# Attenuverting_Mixer_Slim_main_v1.net
KiCad netlist of a schematic drawn in EAGLE
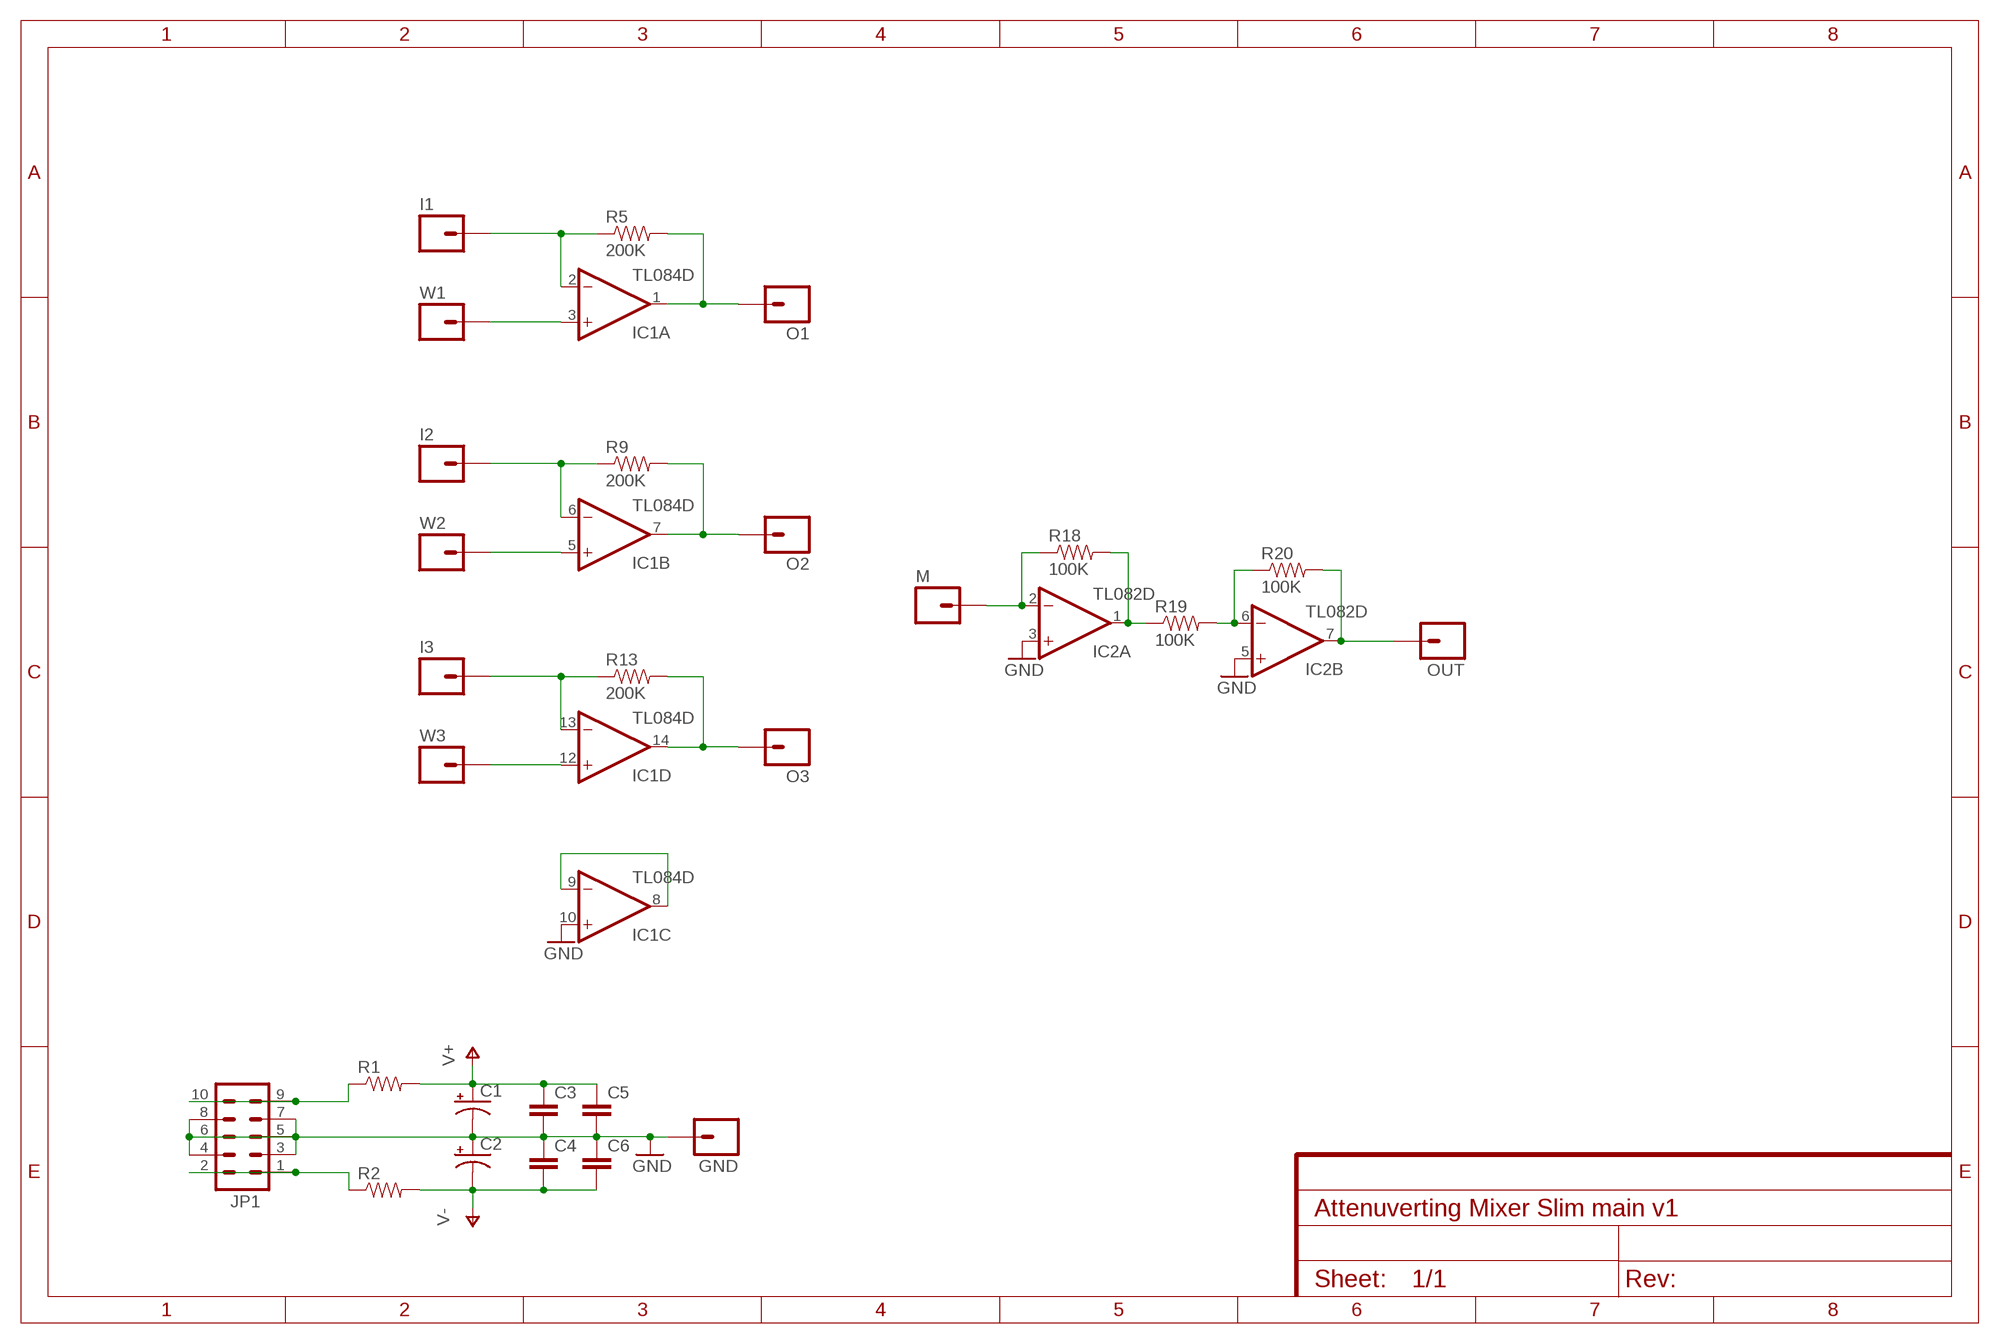
[diagram p0: schematic, sheet 1]

(export (version "E")
  (design (tool "Eeschema 10.0.6"))
  (components
    (comp (ref "C1")
      (value "CAP_POLC")
      (footprint "eagle-import:PANASONIC_C")
      (libsource (lib "eagle-import") (part "CAP_POLC"))
    )
    (comp (ref "C2")
      (value "CAP_POLC")
      (footprint "eagle-import:PANASONIC_C")
      (libsource (lib "eagle-import") (part "CAP_POLC"))
    )
    (comp (ref "C3")
      (value "CAP0603-CAP")
      (footprint "eagle-import:0603-CAP")
      (libsource (lib "eagle-import") (part "CAP0603-CAP"))
    )
    (comp (ref "C4")
      (value "CAP0603-CAP")
      (footprint "eagle-import:0603-CAP")
      (libsource (lib "eagle-import") (part "CAP0603-CAP"))
    )
    (comp (ref "C5")
      (value "CAP0603-CAP")
      (footprint "eagle-import:0603-CAP")
      (libsource (lib "eagle-import") (part "CAP0603-CAP"))
    )
    (comp (ref "C6")
      (value "CAP0603-CAP")
      (footprint "eagle-import:0603-CAP")
      (libsource (lib "eagle-import") (part "CAP0603-CAP"))
    )
    (comp (ref "GND")
      (value "M01PTH")
      (footprint "eagle-import:1X01")
      (libsource (lib "eagle-import") (part "M01PTH"))
    )
    (comp (ref "I1")
      (value "M01PTH")
      (footprint "eagle-import:1X01")
      (libsource (lib "eagle-import") (part "M01PTH"))
    )
    (comp (ref "I2")
      (value "M01PTH")
      (footprint "eagle-import:1X01")
      (libsource (lib "eagle-import") (part "M01PTH"))
    )
    (comp (ref "I3")
      (value "M01PTH")
      (footprint "eagle-import:1X01")
      (libsource (lib "eagle-import") (part "M01PTH"))
    )
    (comp (ref "IC1")
      (value "TL084D")
      (footprint "eagle-import:SO14")
      (libsource (lib "eagle-import") (part "TL084D"))
    )
    (comp (ref "IC2")
      (value "TL082D")
      (footprint "eagle-import:SO08")
      (libsource (lib "eagle-import") (part "TL082D"))
    )
    (comp (ref "JP1")
      (value "M05X2PTH")
      (footprint "eagle-import:AVR_ICSP")
      (libsource (lib "eagle-import") (part "M05X2PTH"))
    )
    (comp (ref "M")
      (value "M01PTH")
      (footprint "eagle-import:1X01")
      (libsource (lib "eagle-import") (part "M01PTH"))
    )
    (comp (ref "O1")
      (value "M01PTH")
      (footprint "eagle-import:1X01")
      (libsource (lib "eagle-import") (part "M01PTH"))
    )
    (comp (ref "O2")
      (value "M01PTH")
      (footprint "eagle-import:1X01")
      (libsource (lib "eagle-import") (part "M01PTH"))
    )
    (comp (ref "O3")
      (value "M01PTH")
      (footprint "eagle-import:1X01")
      (libsource (lib "eagle-import") (part "M01PTH"))
    )
    (comp (ref "OUT")
      (value "M01PTH")
      (footprint "eagle-import:1X01")
      (libsource (lib "eagle-import") (part "M01PTH"))
    )
    (comp (ref "R1")
      (value "RESISTOR0805-RES")
      (footprint "eagle-import:0805")
      (libsource (lib "eagle-import") (part "SparkFun-Resistors_RESISTOR0805-RES"))
    )
    (comp (ref "R2")
      (value "RESISTOR0805-RES")
      (footprint "eagle-import:0805")
      (libsource (lib "eagle-import") (part "SparkFun-Resistors_RESISTOR0805-RES"))
    )
    (comp (ref "R5")
      (value "200K")
      (footprint "eagle-import:0603-RES")
      (libsource (lib "eagle-import") (part "RESISTOR0603-RES"))
    )
    (comp (ref "R9")
      (value "200K")
      (footprint "eagle-import:0603-RES")
      (libsource (lib "eagle-import") (part "RESISTOR0603-RES"))
    )
    (comp (ref "R13")
      (value "200K")
      (footprint "eagle-import:0603-RES")
      (libsource (lib "eagle-import") (part "RESISTOR0603-RES"))
    )
    (comp (ref "R18")
      (value "100K")
      (footprint "eagle-import:0603-RES")
      (libsource (lib "eagle-import") (part "RESISTOR0603-RES"))
    )
    (comp (ref "R19")
      (value "100K")
      (footprint "eagle-import:0603-RES")
      (libsource (lib "eagle-import") (part "RESISTOR0603-RES"))
    )
    (comp (ref "R20")
      (value "100K")
      (footprint "eagle-import:0603-RES")
      (libsource (lib "eagle-import") (part "RESISTOR0603-RES"))
    )
    (comp (ref "W1")
      (value "M01PTH")
      (footprint "eagle-import:1X01")
      (libsource (lib "eagle-import") (part "M01PTH"))
    )
    (comp (ref "W2")
      (value "M01PTH")
      (footprint "eagle-import:1X01")
      (libsource (lib "eagle-import") (part "M01PTH"))
    )
    (comp (ref "W3")
      (value "M01PTH")
      (footprint "eagle-import:1X01")
      (libsource (lib "eagle-import") (part "M01PTH"))
    )
  )
  (nets
    (net (code "1") (name "GND") (class "Default")
      (node (ref "C1") (pin "-") (pinfunction "-_-") (pintype "passive"))
      (node (ref "C2") (pin "+") (pinfunction "+_+") (pintype "passive"))
      (node (ref "C3") (pin "2") (pinfunction "2_2") (pintype "passive"))
      (node (ref "C4") (pin "1") (pinfunction "1_1") (pintype "passive"))
      (node (ref "C5") (pin "2") (pinfunction "2_2") (pintype "passive"))
      (node (ref "C6") (pin "1") (pinfunction "1_1") (pintype "passive"))
      (node (ref "GND") (pin "1") (pinfunction "1_1") (pintype "passive"))
      (node (ref "IC1") (pin "10") (pinfunction "+IN_10") (pintype "input"))
      (node (ref "IC2") (pin "3") (pinfunction "+IN_3") (pintype "input"))
      (node (ref "IC2") (pin "5") (pinfunction "+IN_5") (pintype "input"))
      (node (ref "JP1") (pin "3") (pinfunction "3_3") (pintype "passive"))
      (node (ref "JP1") (pin "4") (pinfunction "4_4") (pintype "passive"))
      (node (ref "JP1") (pin "5") (pinfunction "5_5") (pintype "passive"))
      (node (ref "JP1") (pin "6") (pinfunction "6_6") (pintype "passive"))
      (node (ref "JP1") (pin "7") (pinfunction "7_7") (pintype "passive"))
      (node (ref "JP1") (pin "8") (pinfunction "8_8") (pintype "passive"))
    )
    (net (code "2") (name "Net-(IC1A-+IN)") (class "Default")
      (node (ref "IC1") (pin "3") (pinfunction "+IN_3") (pintype "input"))
      (node (ref "W1") (pin "1") (pinfunction "1_1") (pintype "passive"))
    )
    (net (code "3") (name "Net-(IC1A--IN)") (class "Default")
      (node (ref "I1") (pin "1") (pinfunction "1_1") (pintype "passive"))
      (node (ref "IC1") (pin "2") (pinfunction "-IN_2") (pintype "input"))
      (node (ref "R5") (pin "1") (pinfunction "1_1") (pintype "passive"))
    )
    (net (code "4") (name "Net-(IC1A-OUT)") (class "Default")
      (node (ref "IC1") (pin "1") (pinfunction "OUT_1") (pintype "output"))
      (node (ref "O1") (pin "1") (pinfunction "1_1") (pintype "passive"))
      (node (ref "R5") (pin "2") (pinfunction "2_2") (pintype "passive"))
    )
    (net (code "5") (name "Net-(IC1B-+IN)") (class "Default")
      (node (ref "IC1") (pin "5") (pinfunction "+IN_5") (pintype "input"))
      (node (ref "W2") (pin "1") (pinfunction "1_1") (pintype "passive"))
    )
    (net (code "6") (name "Net-(IC1B--IN)") (class "Default")
      (node (ref "I2") (pin "1") (pinfunction "1_1") (pintype "passive"))
      (node (ref "IC1") (pin "6") (pinfunction "-IN_6") (pintype "input"))
      (node (ref "R9") (pin "1") (pinfunction "1_1") (pintype "passive"))
    )
    (net (code "7") (name "Net-(IC1B-OUT)") (class "Default")
      (node (ref "IC1") (pin "7") (pinfunction "OUT_7") (pintype "output"))
      (node (ref "O2") (pin "1") (pinfunction "1_1") (pintype "passive"))
      (node (ref "R9") (pin "2") (pinfunction "2_2") (pintype "passive"))
    )
    (net (code "8") (name "Net-(IC1C--IN)") (class "Default")
      (node (ref "IC1") (pin "8") (pinfunction "OUT_8") (pintype "output"))
      (node (ref "IC1") (pin "9") (pinfunction "-IN_9") (pintype "input"))
    )
    (net (code "9") (name "Net-(IC1D-+IN)") (class "Default")
      (node (ref "IC1") (pin "12") (pinfunction "+IN_12") (pintype "input"))
      (node (ref "W3") (pin "1") (pinfunction "1_1") (pintype "passive"))
    )
    (net (code "10") (name "Net-(IC1D--IN)") (class "Default")
      (node (ref "I3") (pin "1") (pinfunction "1_1") (pintype "passive"))
      (node (ref "IC1") (pin "13") (pinfunction "-IN_13") (pintype "input"))
      (node (ref "R13") (pin "1") (pinfunction "1_1") (pintype "passive"))
    )
    (net (code "11") (name "Net-(IC1D-OUT)") (class "Default")
      (node (ref "IC1") (pin "14") (pinfunction "OUT_14") (pintype "output"))
      (node (ref "O3") (pin "1") (pinfunction "1_1") (pintype "passive"))
      (node (ref "R13") (pin "2") (pinfunction "2_2") (pintype "passive"))
    )
    (net (code "12") (name "Net-(IC2A--IN)") (class "Default")
      (node (ref "IC2") (pin "2") (pinfunction "-IN_2") (pintype "input"))
      (node (ref "M") (pin "1") (pinfunction "1_1") (pintype "passive"))
      (node (ref "R18") (pin "1") (pinfunction "1_1") (pintype "passive"))
    )
    (net (code "13") (name "Net-(IC2A-OUT)") (class "Default")
      (node (ref "IC2") (pin "1") (pinfunction "OUT_1") (pintype "output"))
      (node (ref "R18") (pin "2") (pinfunction "2_2") (pintype "passive"))
      (node (ref "R19") (pin "1") (pinfunction "1_1") (pintype "passive"))
    )
    (net (code "14") (name "Net-(IC2B--IN)") (class "Default")
      (node (ref "IC2") (pin "6") (pinfunction "-IN_6") (pintype "input"))
      (node (ref "R19") (pin "2") (pinfunction "2_2") (pintype "passive"))
      (node (ref "R20") (pin "1") (pinfunction "1_1") (pintype "passive"))
    )
    (net (code "15") (name "Net-(IC2B-OUT)") (class "Default")
      (node (ref "IC2") (pin "7") (pinfunction "OUT_7") (pintype "output"))
      (node (ref "OUT") (pin "1") (pinfunction "1_1") (pintype "passive"))
      (node (ref "R20") (pin "2") (pinfunction "2_2") (pintype "passive"))
    )
    (net (code "16") (name "Net-(JP1-Pad1)") (class "Default")
      (node (ref "JP1") (pin "1") (pinfunction "1_1") (pintype "passive"))
      (node (ref "JP1") (pin "2") (pinfunction "2_2") (pintype "passive"))
      (node (ref "R2") (pin "1") (pinfunction "1_1") (pintype "passive"))
    )
    (net (code "17") (name "Net-(JP1-Pad10)") (class "Default")
      (node (ref "JP1") (pin "10") (pinfunction "10_10") (pintype "passive"))
      (node (ref "JP1") (pin "9") (pinfunction "9_9") (pintype "passive"))
      (node (ref "R1") (pin "1") (pinfunction "1_1") (pintype "passive"))
    )
    (net (code "18") (name "V+") (class "Default")
      (node (ref "C1") (pin "+") (pinfunction "+_+") (pintype "passive"))
      (node (ref "C3") (pin "1") (pinfunction "1_1") (pintype "passive"))
      (node (ref "C5") (pin "1") (pinfunction "1_1") (pintype "passive"))
      (node (ref "R1") (pin "2") (pinfunction "2_2") (pintype "passive"))
    )
    (net (code "19") (name "V-") (class "Default")
      (node (ref "C2") (pin "-") (pinfunction "-_-") (pintype "passive"))
      (node (ref "C4") (pin "2") (pinfunction "2_2") (pintype "passive"))
      (node (ref "C6") (pin "2") (pinfunction "2_2") (pintype "passive"))
      (node (ref "R2") (pin "2") (pinfunction "2_2") (pintype "passive"))
    )
  )
)
